# SCH_sensors_2026-05-03.net
KiCad netlist of a schematic drawn in EasyEDA
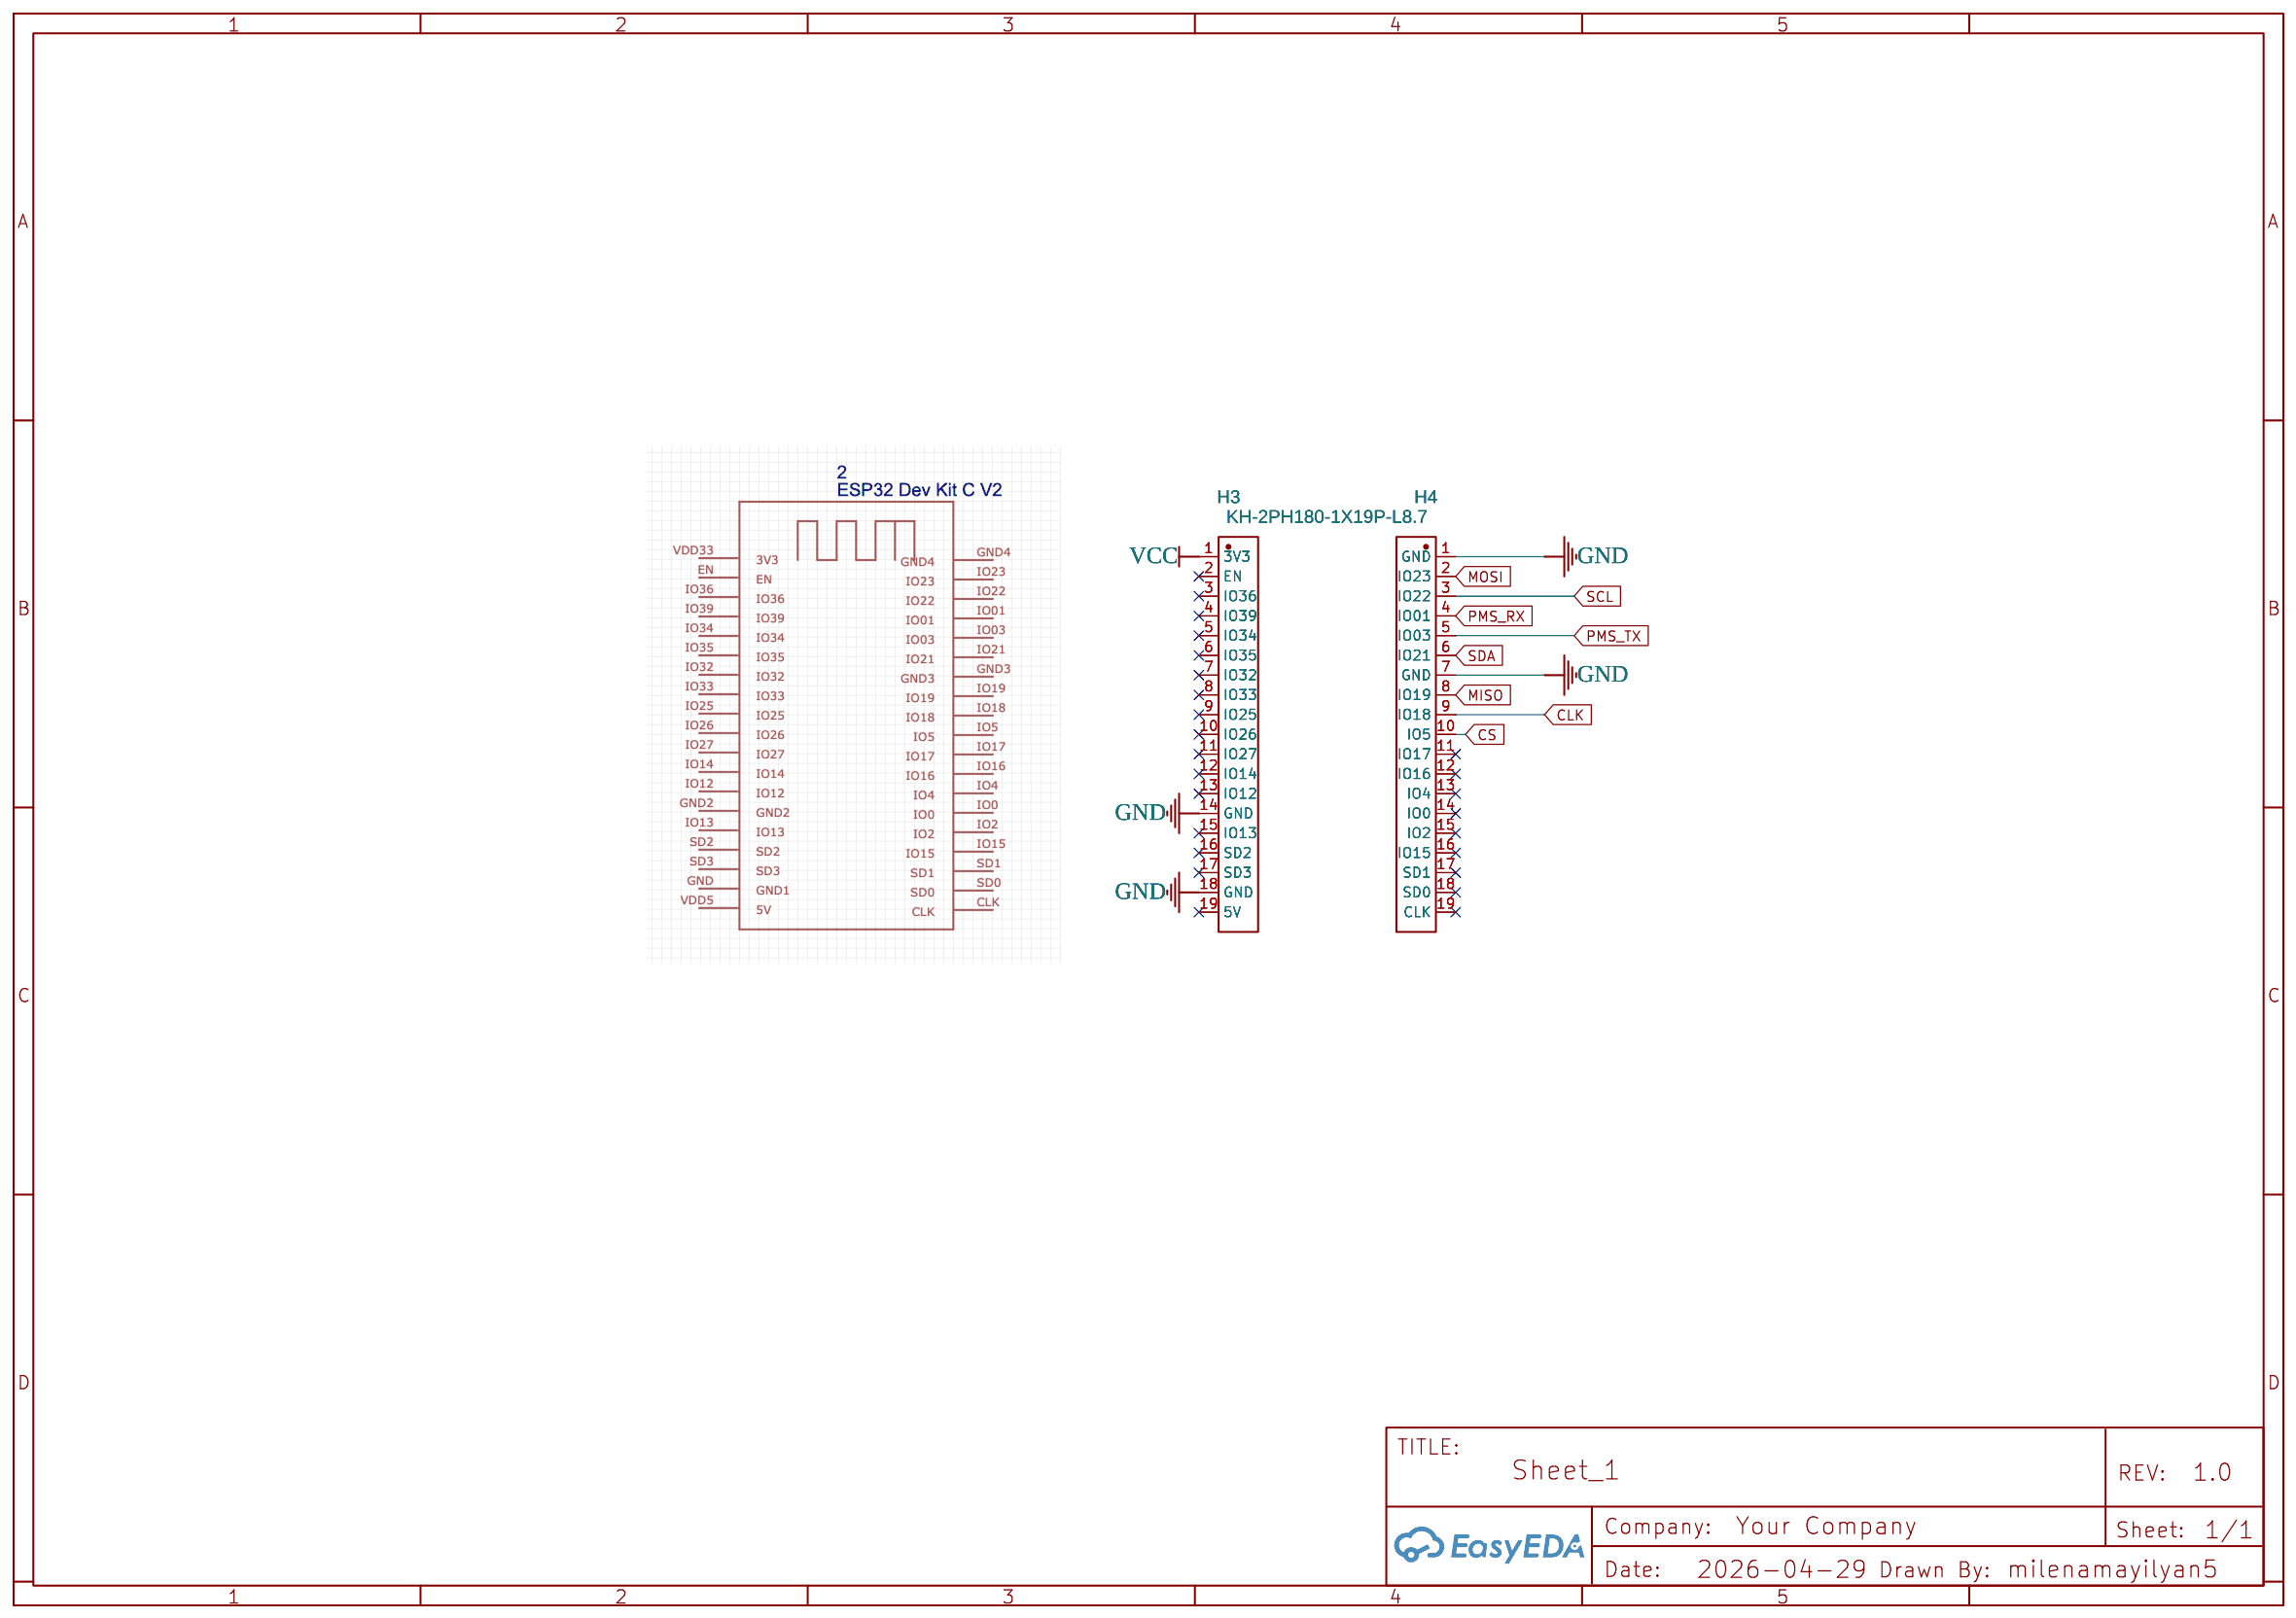
[diagram p0: esp32]
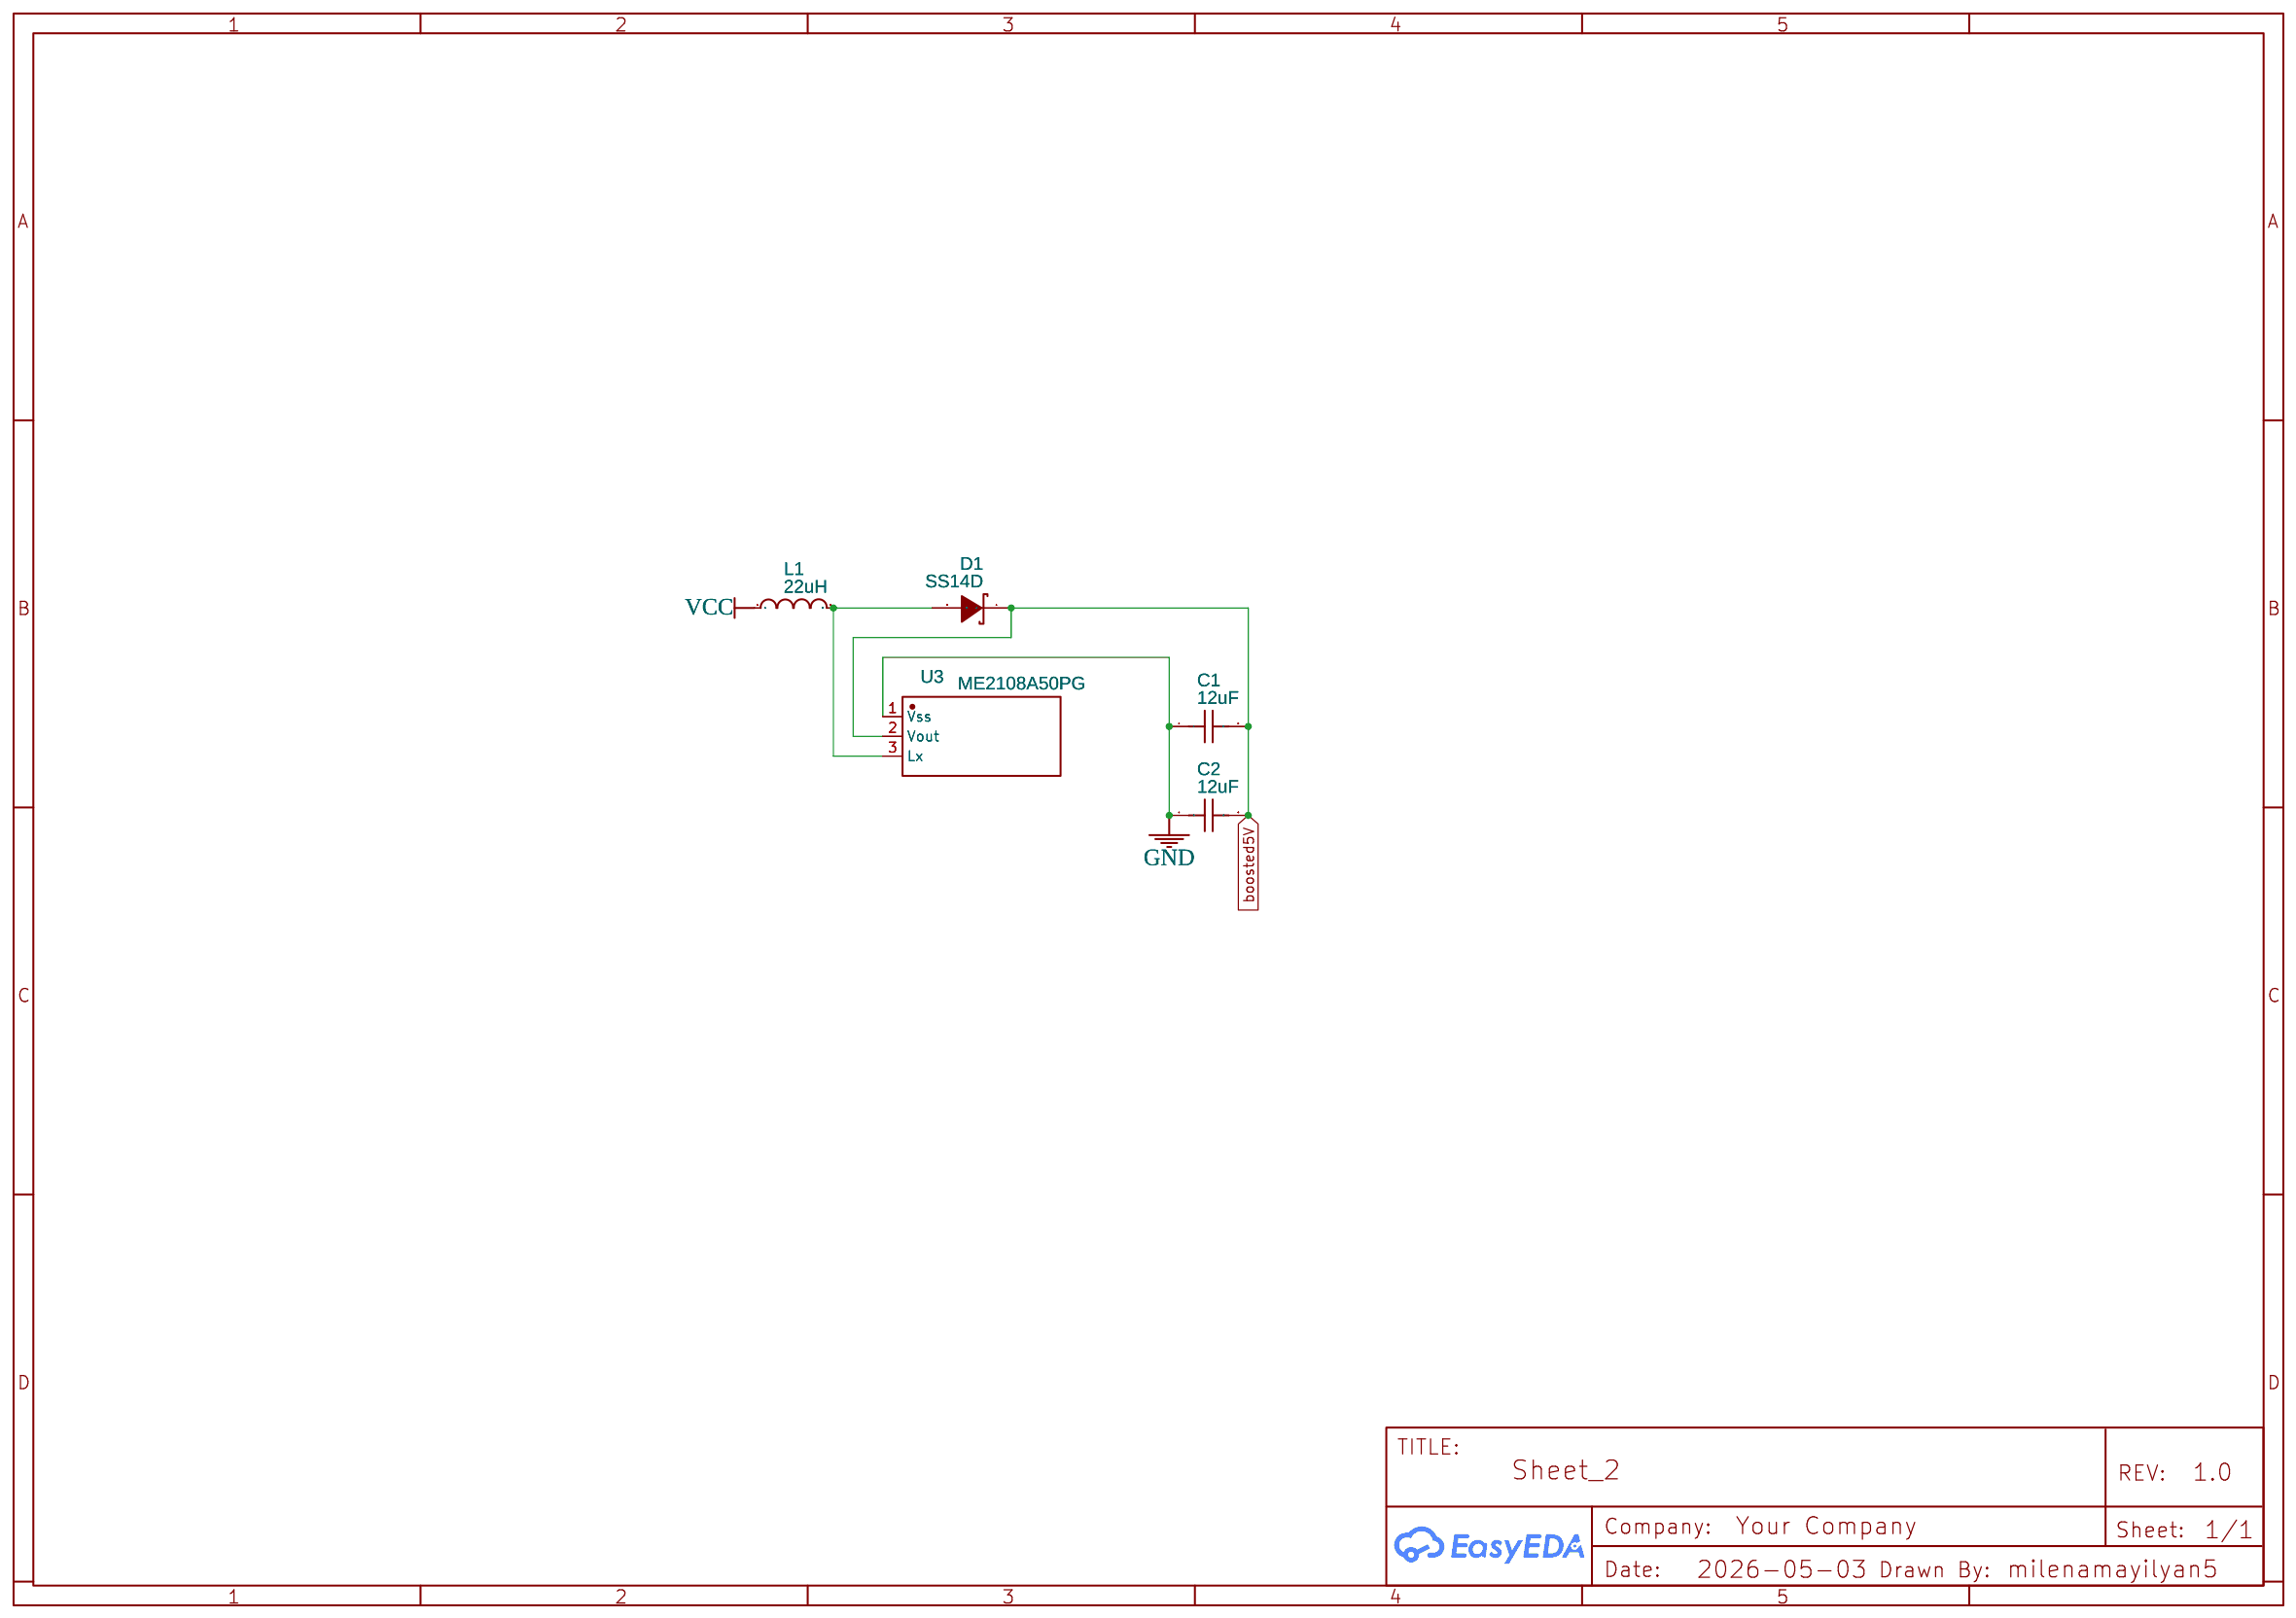
[diagram p1: booster]
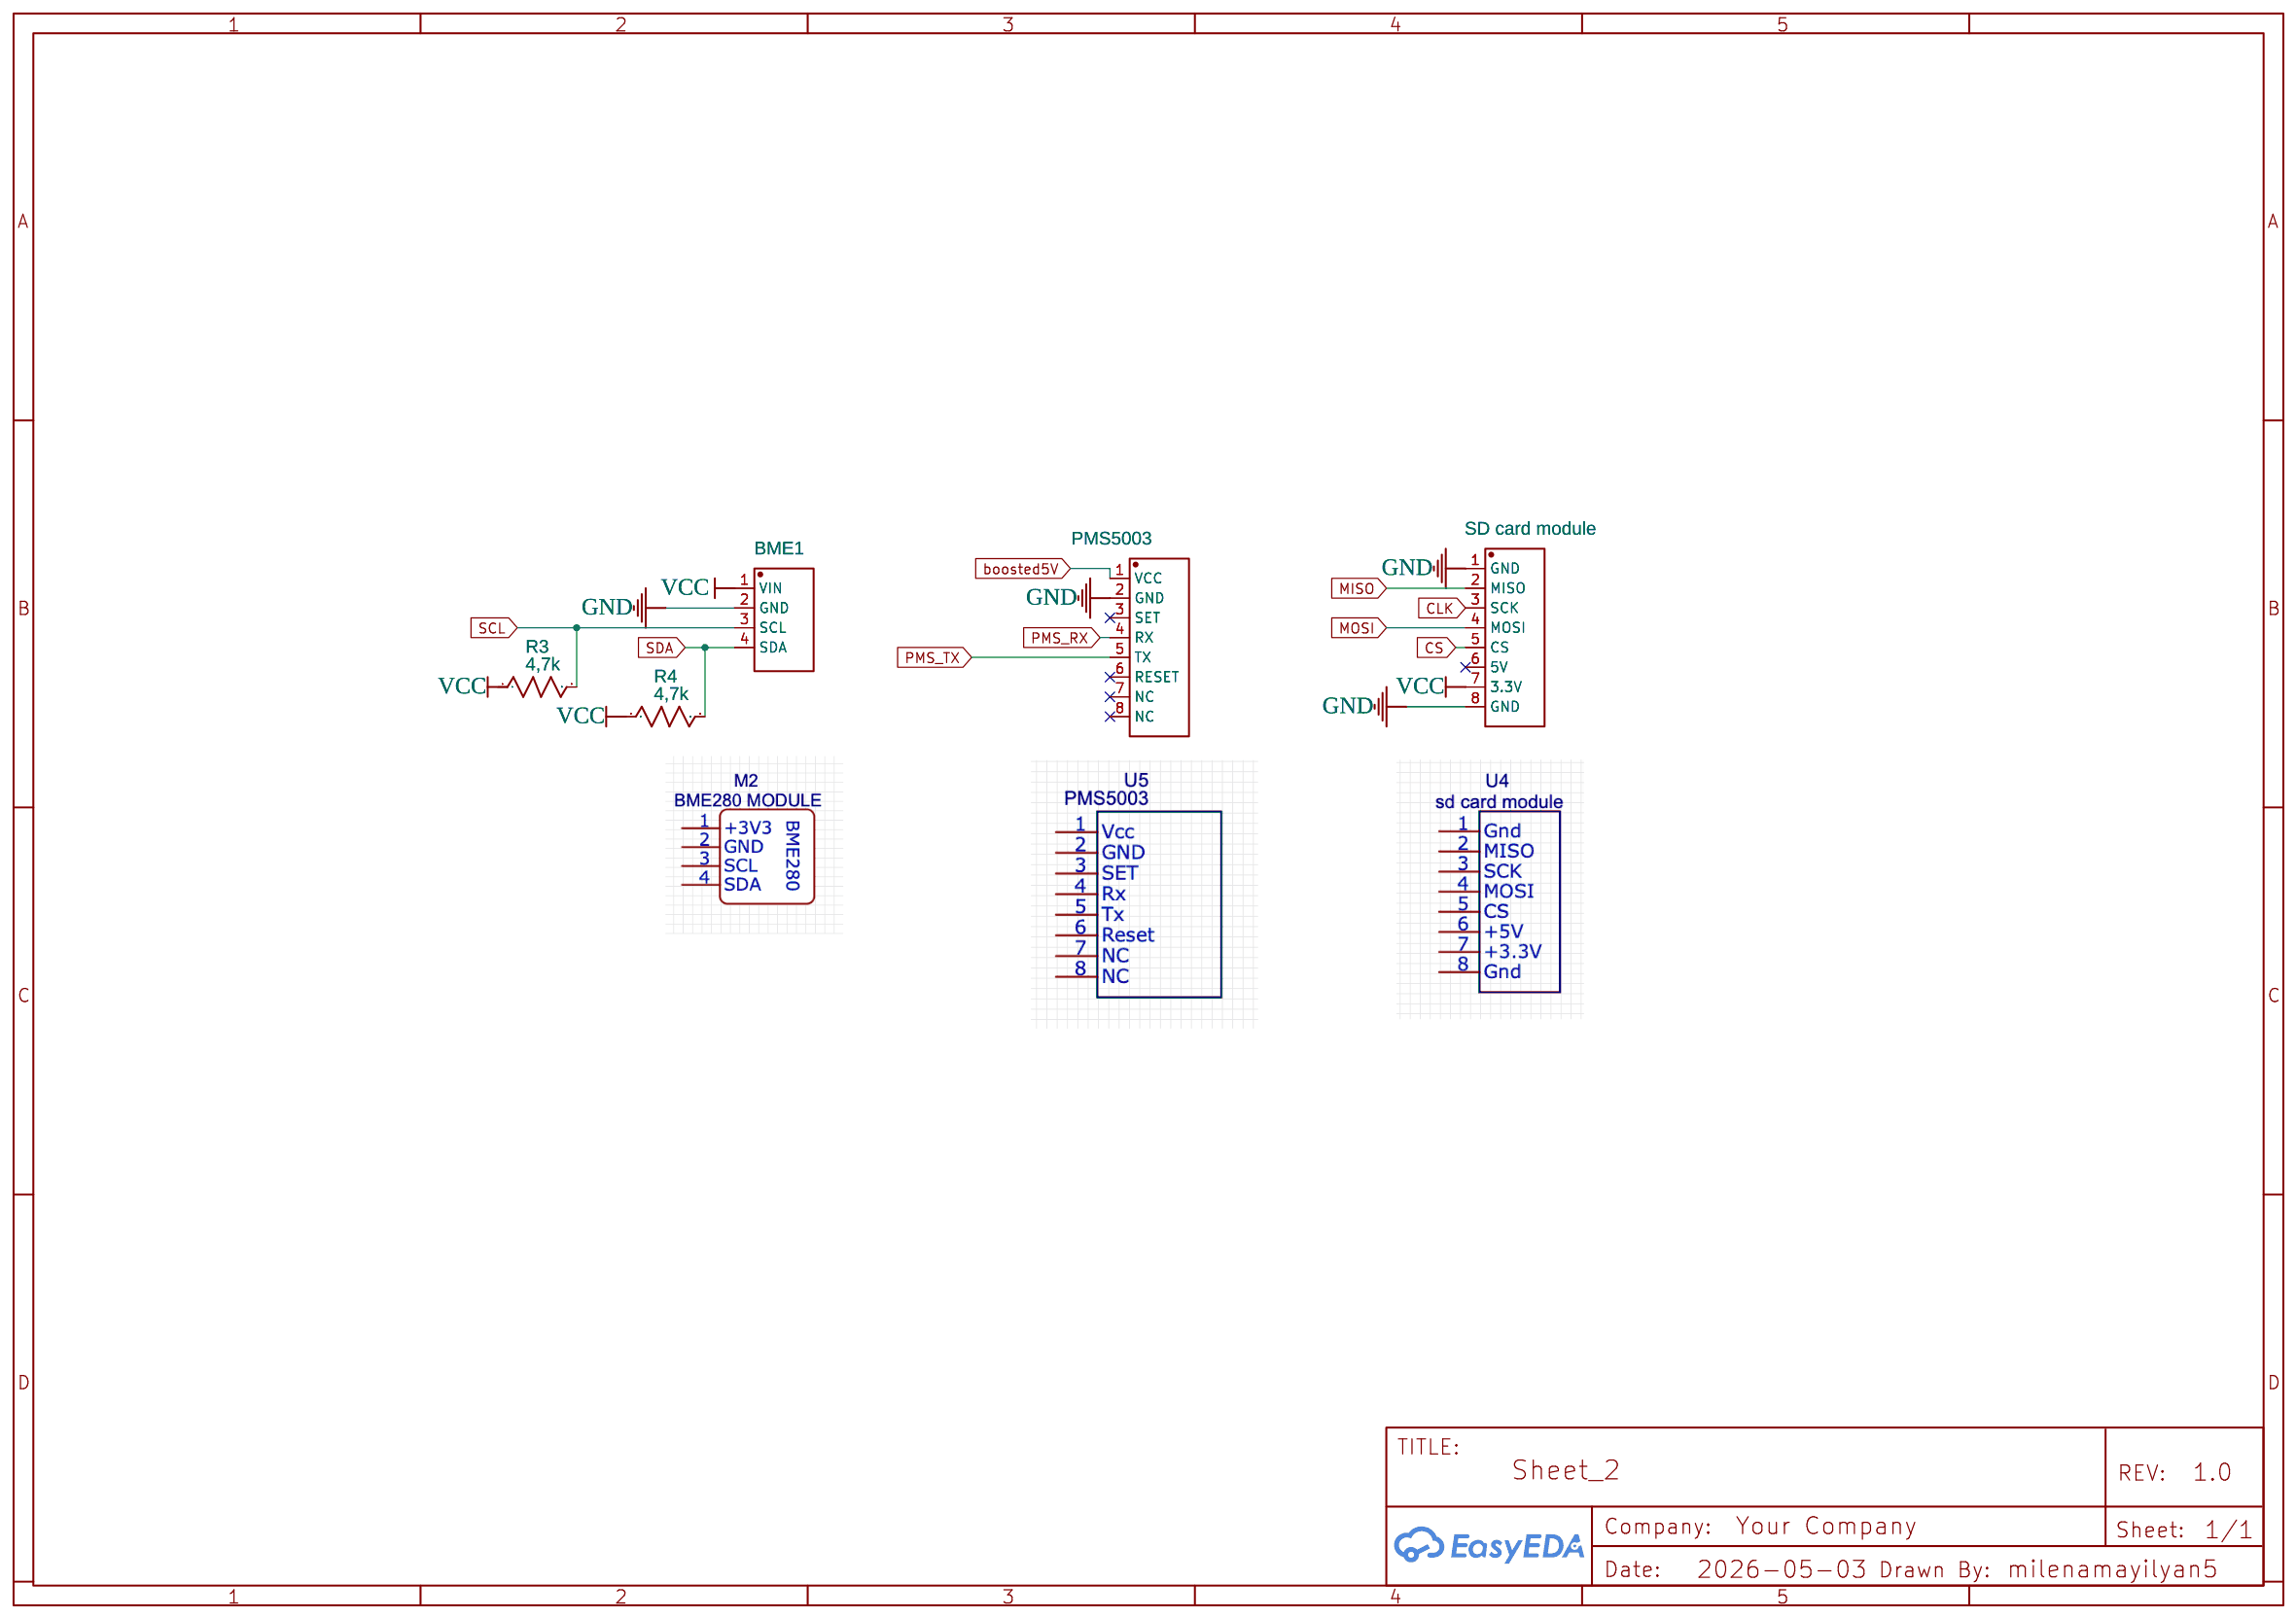
[diagram p2: sensors]

(export (version "E")
  (design (tool "Eeschema 10.0.6"))
  (components
    (comp (ref "H3")
      (value "KH-2PH180-1X19P-L8.7")
      (fields (field (name "Manufacturer") "kinghelm(金航标)"))
      (libsource (lib "") (part "KH-2PH180-1X19P-L8.7_1"))
    )
    (comp (ref "H4")
      (value "KH-2PH180-1X19P-L8.7")
      (fields (field (name "Manufacturer") "kinghelm(金航标)"))
      (libsource (lib "") (part "KH-2PH180-1X19P-L8.7"))
    )
    (comp (ref "C1") (value "12uF") (libsource (lib "") (part "C_0603_US")))
    (comp (ref "C2") (value "12uF") (libsource (lib "") (part "C_0603_US")))
    (comp (ref "D1")
      (value "SS14D")
      (fields (field (name "Manufacturer") "ST(先科)"))
      (libsource (lib "") (part "SS14D"))
    )
    (comp (ref "L1") (value "22uH") (libsource (lib "") (part "L0603_US")))
    (comp (ref "U3")
      (value "ME2108A50PG")
      (fields (field (name "Manufacturer") "MICRONE(南京微盟)"))
      (libsource (lib "") (part "ME2108A50PG"))
    )
    (comp (ref "BME1") (value "I2C RAIL COPY") (libsource (lib "") (part "I2C RAIL COPY")))
    (comp (ref "H5") (value "SD card module") (libsource (lib "") (part "PIN HEADER 2.54 1X8 SCU")))
    (comp (ref "H6") (value "PMS5003") (libsource (lib "") (part "PIN HEADER 2.54 1X8 SCU_1")))
    (comp (ref "R3") (value "4,7k") (libsource (lib "") (part "R_0603_US")))
    (comp (ref "R4") (value "4,7k") (libsource (lib "") (part "R_0603_US")))
  )
  (nets
    (net (code "1") (name "CLK") (class "Default")
      (node (ref "H4") (pin "9") (pinfunction "IO18_9") (pintype "unspecified"))
      (node (ref "H5") (pin "3") (pinfunction "SCK_3") (pintype "unspecified"))
    )
    (net (code "2") (name "CS") (class "Default")
      (node (ref "H4") (pin "10") (pinfunction "IO5_10") (pintype "unspecified"))
      (node (ref "H5") (pin "5") (pinfunction "CS_5") (pintype "unspecified"))
    )
    (net (code "3") (name "GND") (class "Default")
      (node (ref "BME1") (pin "2") (pinfunction "GND_2") (pintype "unspecified"))
      (node (ref "C1") (pin "1") (pinfunction "1_1") (pintype "unspecified"))
      (node (ref "C2") (pin "1") (pinfunction "1_1") (pintype "unspecified"))
      (node (ref "H3") (pin "14") (pinfunction "GND_14") (pintype "unspecified"))
      (node (ref "H3") (pin "18") (pinfunction "GND_18") (pintype "unspecified"))
      (node (ref "H4") (pin "1") (pinfunction "GND_1") (pintype "unspecified"))
      (node (ref "H4") (pin "7") (pinfunction "GND_7") (pintype "unspecified"))
      (node (ref "H5") (pin "1") (pinfunction "GND_1") (pintype "unspecified"))
      (node (ref "H5") (pin "8") (pinfunction "GND_8") (pintype "unspecified"))
      (node (ref "H6") (pin "2") (pinfunction "GND_2") (pintype "unspecified"))
      (node (ref "U3") (pin "1") (pinfunction "Vss_1") (pintype "unspecified"))
    )
    (net (code "4") (name "MISO") (class "Default")
      (node (ref "H4") (pin "8") (pinfunction "IO19_8") (pintype "unspecified"))
      (node (ref "H5") (pin "2") (pinfunction "MISO_2") (pintype "unspecified"))
    )
    (net (code "5") (name "MOSI") (class "Default")
      (node (ref "H4") (pin "2") (pinfunction "IO23_2") (pintype "unspecified"))
      (node (ref "H5") (pin "4") (pinfunction "MOSI_4") (pintype "unspecified"))
    )
    (net (code "6") (name "Net-(D1-A)") (class "Default")
      (node (ref "D1") (pin "2") (pinfunction "A_2") (pintype "unspecified"))
      (node (ref "L1") (pin "2") (pinfunction "2_2") (pintype "unspecified"))
      (node (ref "U3") (pin "3") (pinfunction "Lx_3") (pintype "unspecified"))
    )
    (net (code "7") (name "PMS_RX") (class "Default")
      (node (ref "H4") (pin "4") (pinfunction "IO01_4") (pintype "unspecified"))
      (node (ref "H6") (pin "4") (pinfunction "RX_4") (pintype "unspecified"))
    )
    (net (code "8") (name "PMS_TX") (class "Default")
      (node (ref "H4") (pin "5") (pinfunction "IO03_5") (pintype "unspecified"))
      (node (ref "H6") (pin "5") (pinfunction "TX_5") (pintype "unspecified"))
    )
    (net (code "9") (name "SCL") (class "Default")
      (node (ref "BME1") (pin "3") (pinfunction "SCL_3") (pintype "unspecified"))
      (node (ref "H4") (pin "3") (pinfunction "IO22_3") (pintype "unspecified"))
      (node (ref "R3") (pin "2") (pinfunction "2_2") (pintype "unspecified"))
    )
    (net (code "10") (name "SDA") (class "Default")
      (node (ref "BME1") (pin "4") (pinfunction "SDA_4") (pintype "unspecified"))
      (node (ref "H4") (pin "6") (pinfunction "IO21_6") (pintype "unspecified"))
      (node (ref "R4") (pin "2") (pinfunction "2_2") (pintype "unspecified"))
    )
    (net (code "11") (name "VCC") (class "Default")
      (node (ref "BME1") (pin "1") (pinfunction "VIN_1") (pintype "unspecified"))
      (node (ref "H3") (pin "1") (pinfunction "3V3_1") (pintype "unspecified"))
      (node (ref "H5") (pin "7") (pinfunction "3.3V_7") (pintype "unspecified"))
      (node (ref "L1") (pin "1") (pinfunction "1_1") (pintype "unspecified"))
      (node (ref "R3") (pin "1") (pinfunction "1_1") (pintype "unspecified"))
      (node (ref "R4") (pin "1") (pinfunction "1_1") (pintype "unspecified"))
    )
    (net (code "12") (name "boosted5V") (class "Default")
      (node (ref "C1") (pin "2") (pinfunction "2_2") (pintype "unspecified"))
      (node (ref "C2") (pin "2") (pinfunction "2_2") (pintype "unspecified"))
      (node (ref "D1") (pin "1") (pinfunction "K_1") (pintype "unspecified"))
      (node (ref "H6") (pin "1") (pinfunction "VCC_1") (pintype "unspecified"))
      (node (ref "U3") (pin "2") (pinfunction "Vout_2") (pintype "unspecified"))
    )
    (net (code "13") (name "unconnected-(H3-5V-Pad19)") (class "Default")
      (node (ref "H3") (pin "19") (pinfunction "5V_19") (pintype "unspecified+no_connect"))
    )
    (net (code "14") (name "unconnected-(H3-EN-Pad2)") (class "Default")
      (node (ref "H3") (pin "2") (pinfunction "EN_2") (pintype "unspecified+no_connect"))
    )
    (net (code "15") (name "unconnected-(H3-IO12-Pad13)") (class "Default")
      (node (ref "H3") (pin "13") (pinfunction "IO12_13") (pintype "unspecified+no_connect"))
    )
    (net (code "16") (name "unconnected-(H3-IO13-Pad15)") (class "Default")
      (node (ref "H3") (pin "15") (pinfunction "IO13_15") (pintype "unspecified+no_connect"))
    )
    (net (code "17") (name "unconnected-(H3-IO14-Pad12)") (class "Default")
      (node (ref "H3") (pin "12") (pinfunction "IO14_12") (pintype "unspecified+no_connect"))
    )
    (net (code "18") (name "unconnected-(H3-IO25-Pad9)") (class "Default")
      (node (ref "H3") (pin "9") (pinfunction "IO25_9") (pintype "unspecified+no_connect"))
    )
    (net (code "19") (name "unconnected-(H3-IO26-Pad10)") (class "Default")
      (node (ref "H3") (pin "10") (pinfunction "IO26_10") (pintype "unspecified+no_connect"))
    )
    (net (code "20") (name "unconnected-(H3-IO27-Pad11)") (class "Default")
      (node (ref "H3") (pin "11") (pinfunction "IO27_11") (pintype "unspecified+no_connect"))
    )
    (net (code "21") (name "unconnected-(H3-IO32-Pad7)") (class "Default")
      (node (ref "H3") (pin "7") (pinfunction "IO32_7") (pintype "unspecified+no_connect"))
    )
    (net (code "22") (name "unconnected-(H3-IO33-Pad8)") (class "Default")
      (node (ref "H3") (pin "8") (pinfunction "IO33_8") (pintype "unspecified+no_connect"))
    )
    (net (code "23") (name "unconnected-(H3-IO34-Pad5)") (class "Default")
      (node (ref "H3") (pin "5") (pinfunction "IO34_5") (pintype "unspecified+no_connect"))
    )
    (net (code "24") (name "unconnected-(H3-IO35-Pad6)") (class "Default")
      (node (ref "H3") (pin "6") (pinfunction "IO35_6") (pintype "unspecified+no_connect"))
    )
    (net (code "25") (name "unconnected-(H3-IO36-Pad3)") (class "Default")
      (node (ref "H3") (pin "3") (pinfunction "IO36_3") (pintype "unspecified+no_connect"))
    )
    (net (code "26") (name "unconnected-(H3-IO39-Pad4)") (class "Default")
      (node (ref "H3") (pin "4") (pinfunction "IO39_4") (pintype "unspecified+no_connect"))
    )
    (net (code "27") (name "unconnected-(H3-SD2-Pad16)") (class "Default")
      (node (ref "H3") (pin "16") (pinfunction "SD2_16") (pintype "unspecified+no_connect"))
    )
    (net (code "28") (name "unconnected-(H3-SD3-Pad17)") (class "Default")
      (node (ref "H3") (pin "17") (pinfunction "SD3_17") (pintype "unspecified+no_connect"))
    )
    (net (code "29") (name "unconnected-(H4-CLK-Pad19)") (class "Default")
      (node (ref "H4") (pin "19") (pinfunction "CLK_19") (pintype "unspecified+no_connect"))
    )
    (net (code "30") (name "unconnected-(H4-IO0-Pad14)") (class "Default")
      (node (ref "H4") (pin "14") (pinfunction "IO0_14") (pintype "unspecified+no_connect"))
    )
    (net (code "31") (name "unconnected-(H4-IO2-Pad15)") (class "Default")
      (node (ref "H4") (pin "15") (pinfunction "IO2_15") (pintype "unspecified+no_connect"))
    )
    (net (code "32") (name "unconnected-(H4-IO4-Pad13)") (class "Default")
      (node (ref "H4") (pin "13") (pinfunction "IO4_13") (pintype "unspecified+no_connect"))
    )
    (net (code "33") (name "unconnected-(H4-IO15-Pad16)") (class "Default")
      (node (ref "H4") (pin "16") (pinfunction "IO15_16") (pintype "unspecified+no_connect"))
    )
    (net (code "34") (name "unconnected-(H4-IO16-Pad12)") (class "Default")
      (node (ref "H4") (pin "12") (pinfunction "IO16_12") (pintype "unspecified+no_connect"))
    )
    (net (code "35") (name "unconnected-(H4-IO17-Pad11)") (class "Default")
      (node (ref "H4") (pin "11") (pinfunction "IO17_11") (pintype "unspecified+no_connect"))
    )
    (net (code "36") (name "unconnected-(H4-SD0-Pad18)") (class "Default")
      (node (ref "H4") (pin "18") (pinfunction "SD0_18") (pintype "unspecified+no_connect"))
    )
    (net (code "37") (name "unconnected-(H4-SD1-Pad17)") (class "Default")
      (node (ref "H4") (pin "17") (pinfunction "SD1_17") (pintype "unspecified+no_connect"))
    )
    (net (code "38") (name "unconnected-(H5-5V-Pad6)") (class "Default")
      (node (ref "H5") (pin "6") (pinfunction "5V_6") (pintype "unspecified+no_connect"))
    )
    (net (code "39") (name "unconnected-(H6-NC-Pad7)") (class "Default")
      (node (ref "H6") (pin "7") (pinfunction "NC_7") (pintype "unspecified+no_connect"))
    )
    (net (code "40") (name "unconnected-(H6-NC-Pad8)") (class "Default")
      (node (ref "H6") (pin "8") (pinfunction "NC_8") (pintype "unspecified+no_connect"))
    )
    (net (code "41") (name "unconnected-(H6-RESET-Pad6)") (class "Default")
      (node (ref "H6") (pin "6") (pinfunction "RESET_6") (pintype "unspecified+no_connect"))
    )
    (net (code "42") (name "unconnected-(H6-SET-Pad3)") (class "Default")
      (node (ref "H6") (pin "3") (pinfunction "SET_3") (pintype "unspecified+no_connect"))
    )
  )
)
